# ADC_Board_Left.net
KiCad netlist of a schematic drawn in EAGLE
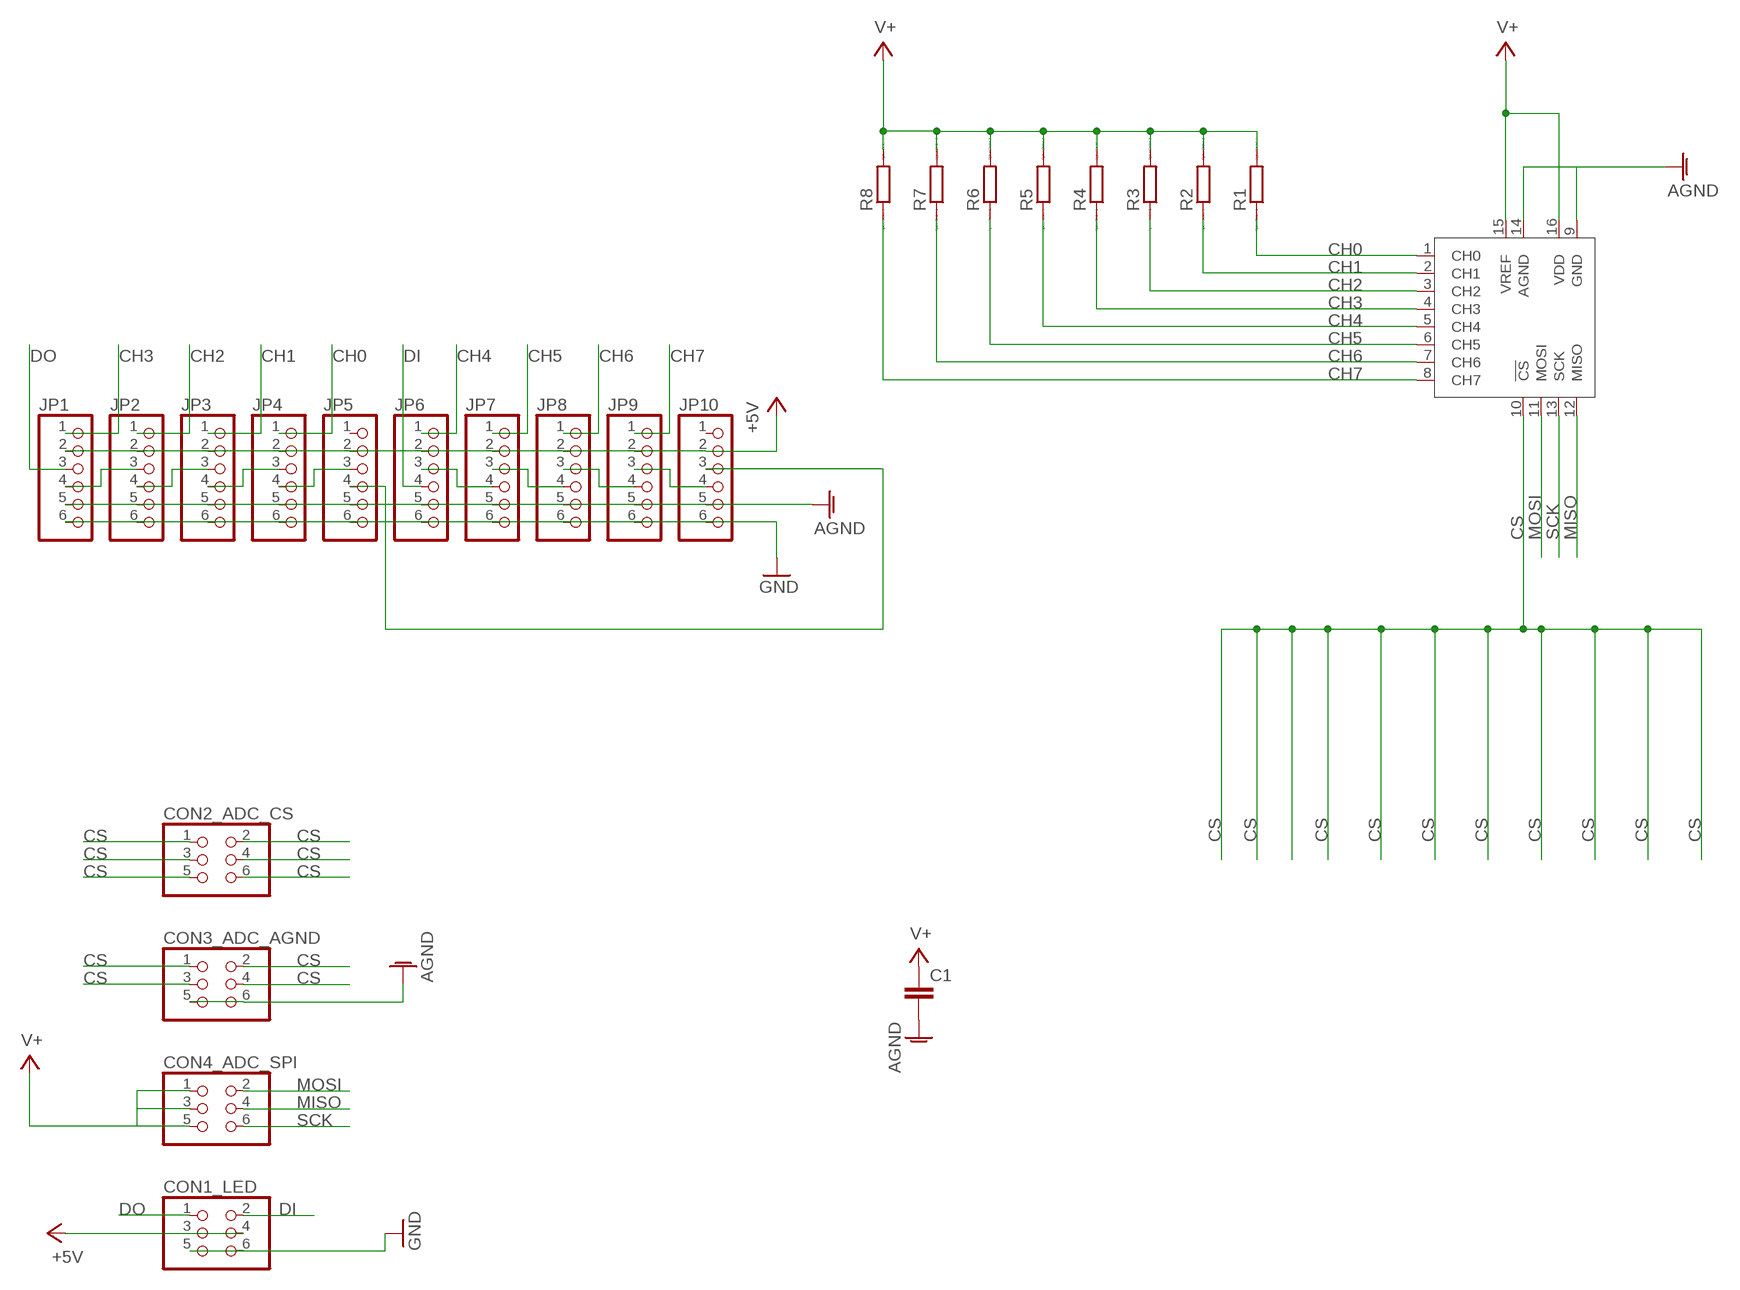
[diagram p0: schematic, sheet 1]

(export (version "E")
  (design (tool "Eeschema 10.0.6"))
  (components
    (comp (ref "C1")
      (value "C-EU050-025X075")
      (footprint "eagle-import:C050-025X075")
      (libsource (lib "eagle-import") (part "C-EU050-025X075"))
    )
    (comp (ref "CON1_LED")
      (value "PINHD-2X3")
      (footprint "eagle-import:2X03")
      (libsource (lib "eagle-import") (part "PINHD-2X3"))
    )
    (comp (ref "CON2_ADC_CS")
      (value "PINHD-2X3")
      (footprint "eagle-import:2X03")
      (libsource (lib "eagle-import") (part "PINHD-2X3"))
    )
    (comp (ref "CON3_ADC_AGND")
      (value "PINHD-2X3")
      (footprint "eagle-import:2X03")
      (libsource (lib "eagle-import") (part "PINHD-2X3"))
    )
    (comp (ref "CON4_ADC_SPI")
      (value "PINHD-2X3")
      (footprint "eagle-import:2X03")
      (libsource (lib "eagle-import") (part "PINHD-2X3"))
    )
    (comp (ref "JP1")
      (value "PINHD-1X6")
      (footprint "eagle-import:1X06")
      (libsource (lib "eagle-import") (part "PINHD-1X6"))
    )
    (comp (ref "JP2")
      (value "PINHD-1X6")
      (footprint "eagle-import:1X06")
      (libsource (lib "eagle-import") (part "PINHD-1X6"))
    )
    (comp (ref "JP3")
      (value "PINHD-1X6")
      (footprint "eagle-import:1X06")
      (libsource (lib "eagle-import") (part "PINHD-1X6"))
    )
    (comp (ref "JP4")
      (value "PINHD-1X6")
      (footprint "eagle-import:1X06")
      (libsource (lib "eagle-import") (part "PINHD-1X6"))
    )
    (comp (ref "JP5")
      (value "PINHD-1X6")
      (footprint "eagle-import:1X06")
      (libsource (lib "eagle-import") (part "PINHD-1X6"))
    )
    (comp (ref "JP6")
      (value "PINHD-1X6")
      (footprint "eagle-import:1X06")
      (libsource (lib "eagle-import") (part "PINHD-1X6"))
    )
    (comp (ref "JP7")
      (value "PINHD-1X6")
      (footprint "eagle-import:1X06")
      (libsource (lib "eagle-import") (part "PINHD-1X6"))
    )
    (comp (ref "JP8")
      (value "PINHD-1X6")
      (footprint "eagle-import:1X06")
      (libsource (lib "eagle-import") (part "PINHD-1X6"))
    )
    (comp (ref "JP9")
      (value "PINHD-1X6")
      (footprint "eagle-import:1X06")
      (libsource (lib "eagle-import") (part "PINHD-1X6"))
    )
    (comp (ref "JP10")
      (value "PINHD-1X6")
      (footprint "eagle-import:1X06")
      (libsource (lib "eagle-import") (part "PINHD-1X6"))
    )
    (comp (ref "R1")
      (value "R-EU_0617_22")
      (footprint "eagle-import:0617_22")
      (libsource (lib "eagle-import") (part "R-EU_0617_22"))
    )
    (comp (ref "R2")
      (value "R-EU_0617_22")
      (footprint "eagle-import:0617_22")
      (libsource (lib "eagle-import") (part "R-EU_0617_22"))
    )
    (comp (ref "R3")
      (value "R-EU_0617_22")
      (footprint "eagle-import:0617_22")
      (libsource (lib "eagle-import") (part "R-EU_0617_22"))
    )
    (comp (ref "R4")
      (value "R-EU_0617_22")
      (footprint "eagle-import:0617_22")
      (libsource (lib "eagle-import") (part "R-EU_0617_22"))
    )
    (comp (ref "R5")
      (value "R-EU_0617_22")
      (footprint "eagle-import:0617_22")
      (libsource (lib "eagle-import") (part "R-EU_0617_22"))
    )
    (comp (ref "R6")
      (value "R-EU_0617_22")
      (footprint "eagle-import:0617_22")
      (libsource (lib "eagle-import") (part "R-EU_0617_22"))
    )
    (comp (ref "R7")
      (value "R-EU_0617_22")
      (footprint "eagle-import:0617_22")
      (libsource (lib "eagle-import") (part "R-EU_0617_22"))
    )
    (comp (ref "R8")
      (value "R-EU_0617_22")
      (footprint "eagle-import:0617_22")
      (libsource (lib "eagle-import") (part "R-EU_0617_22"))
    )
    (comp (ref "U$1")
      (value "MCP3008P")
      (footprint "eagle-import:DIL16")
      (libsource (lib "eagle-import") (part "MCP3008P"))
    )
  )
  (nets
    (net (code "1") (name "+5V") (class "Default")
      (node (ref "CON1_LED") (pin "3") (pinfunction "3_3") (pintype "passive"))
      (node (ref "CON1_LED") (pin "4") (pinfunction "4_4") (pintype "passive"))
      (node (ref "JP1") (pin "2") (pinfunction "2_2") (pintype "passive"))
      (node (ref "JP10") (pin "2") (pinfunction "2_2") (pintype "passive"))
      (node (ref "JP2") (pin "2") (pinfunction "2_2") (pintype "passive"))
      (node (ref "JP3") (pin "2") (pinfunction "2_2") (pintype "passive"))
      (node (ref "JP4") (pin "2") (pinfunction "2_2") (pintype "passive"))
      (node (ref "JP5") (pin "2") (pinfunction "2_2") (pintype "passive"))
      (node (ref "JP6") (pin "2") (pinfunction "2_2") (pintype "passive"))
      (node (ref "JP7") (pin "2") (pinfunction "2_2") (pintype "passive"))
      (node (ref "JP8") (pin "2") (pinfunction "2_2") (pintype "passive"))
      (node (ref "JP9") (pin "2") (pinfunction "2_2") (pintype "passive"))
    )
    (net (code "2") (name "/CH0") (class "Default")
      (node (ref "JP4") (pin "1") (pinfunction "1_1") (pintype "passive"))
      (node (ref "R1") (pin "1") (pinfunction "1_1") (pintype "passive"))
      (node (ref "U$1") (pin "1") (pinfunction "CH0_1") (pintype "input"))
    )
    (net (code "3") (name "/CH1") (class "Default")
      (node (ref "JP3") (pin "1") (pinfunction "1_1") (pintype "passive"))
      (node (ref "R2") (pin "1") (pinfunction "1_1") (pintype "passive"))
      (node (ref "U$1") (pin "2") (pinfunction "CH1_2") (pintype "input"))
    )
    (net (code "4") (name "/CH2") (class "Default")
      (node (ref "JP2") (pin "1") (pinfunction "1_1") (pintype "passive"))
      (node (ref "R3") (pin "1") (pinfunction "1_1") (pintype "passive"))
      (node (ref "U$1") (pin "3") (pinfunction "CH2_3") (pintype "input"))
    )
    (net (code "5") (name "/CH3") (class "Default")
      (node (ref "JP1") (pin "1") (pinfunction "1_1") (pintype "passive"))
      (node (ref "R4") (pin "1") (pinfunction "1_1") (pintype "passive"))
      (node (ref "U$1") (pin "4") (pinfunction "CH3_4") (pintype "input"))
    )
    (net (code "6") (name "/CH4") (class "Default")
      (node (ref "JP6") (pin "1") (pinfunction "1_1") (pintype "passive"))
      (node (ref "R5") (pin "1") (pinfunction "1_1") (pintype "passive"))
      (node (ref "U$1") (pin "5") (pinfunction "CH4_5") (pintype "input"))
    )
    (net (code "7") (name "/CH5") (class "Default")
      (node (ref "JP7") (pin "1") (pinfunction "1_1") (pintype "passive"))
      (node (ref "R6") (pin "1") (pinfunction "1_1") (pintype "passive"))
      (node (ref "U$1") (pin "6") (pinfunction "CH5_6") (pintype "input"))
    )
    (net (code "8") (name "/CH6") (class "Default")
      (node (ref "JP8") (pin "1") (pinfunction "1_1") (pintype "passive"))
      (node (ref "R7") (pin "1") (pinfunction "1_1") (pintype "passive"))
      (node (ref "U$1") (pin "7") (pinfunction "CH6_7") (pintype "input"))
    )
    (net (code "9") (name "/CH7") (class "Default")
      (node (ref "JP9") (pin "1") (pinfunction "1_1") (pintype "passive"))
      (node (ref "R8") (pin "1") (pinfunction "1_1") (pintype "passive"))
      (node (ref "U$1") (pin "8") (pinfunction "CH7_8") (pintype "input"))
    )
    (net (code "10") (name "/CS") (class "Default")
      (node (ref "CON2_ADC_CS") (pin "1") (pinfunction "1_1") (pintype "passive"))
      (node (ref "CON2_ADC_CS") (pin "2") (pinfunction "2_2") (pintype "passive"))
      (node (ref "CON2_ADC_CS") (pin "3") (pinfunction "3_3") (pintype "passive"))
      (node (ref "CON2_ADC_CS") (pin "4") (pinfunction "4_4") (pintype "passive"))
      (node (ref "CON2_ADC_CS") (pin "5") (pinfunction "5_5") (pintype "passive"))
      (node (ref "CON2_ADC_CS") (pin "6") (pinfunction "6_6") (pintype "passive"))
      (node (ref "CON3_ADC_AGND") (pin "1") (pinfunction "1_1") (pintype "passive"))
      (node (ref "CON3_ADC_AGND") (pin "2") (pinfunction "2_2") (pintype "passive"))
      (node (ref "CON3_ADC_AGND") (pin "3") (pinfunction "3_3") (pintype "passive"))
      (node (ref "CON3_ADC_AGND") (pin "4") (pinfunction "4_4") (pintype "passive"))
      (node (ref "U$1") (pin "10") (pinfunction "~{CS}_10") (pintype "input"))
    )
    (net (code "11") (name "/DI") (class "Default")
      (node (ref "CON1_LED") (pin "2") (pinfunction "2_2") (pintype "passive"))
      (node (ref "JP6") (pin "4") (pinfunction "4_4") (pintype "passive"))
    )
    (net (code "12") (name "/DO") (class "Default")
      (node (ref "CON1_LED") (pin "1") (pinfunction "1_1") (pintype "passive"))
      (node (ref "JP1") (pin "3") (pinfunction "3_3") (pintype "passive"))
    )
    (net (code "13") (name "/MISO") (class "Default")
      (node (ref "CON4_ADC_SPI") (pin "4") (pinfunction "4_4") (pintype "passive"))
      (node (ref "U$1") (pin "12") (pinfunction "MISO_12") (pintype "output"))
    )
    (net (code "14") (name "/MOSI") (class "Default")
      (node (ref "CON4_ADC_SPI") (pin "2") (pinfunction "2_2") (pintype "passive"))
      (node (ref "U$1") (pin "11") (pinfunction "MOSI_11") (pintype "input"))
    )
    (net (code "15") (name "/SCK") (class "Default")
      (node (ref "CON4_ADC_SPI") (pin "6") (pinfunction "6_6") (pintype "passive"))
      (node (ref "U$1") (pin "13") (pinfunction "SCK_13") (pintype "input"))
    )
    (net (code "16") (name "AGND") (class "Default")
      (node (ref "C1") (pin "2") (pinfunction "2_2") (pintype "passive"))
      (node (ref "CON3_ADC_AGND") (pin "5") (pinfunction "5_5") (pintype "passive"))
      (node (ref "CON3_ADC_AGND") (pin "6") (pinfunction "6_6") (pintype "passive"))
      (node (ref "JP1") (pin "5") (pinfunction "5_5") (pintype "passive"))
      (node (ref "JP10") (pin "5") (pinfunction "5_5") (pintype "passive"))
      (node (ref "JP2") (pin "5") (pinfunction "5_5") (pintype "passive"))
      (node (ref "JP3") (pin "5") (pinfunction "5_5") (pintype "passive"))
      (node (ref "JP4") (pin "5") (pinfunction "5_5") (pintype "passive"))
      (node (ref "JP5") (pin "5") (pinfunction "5_5") (pintype "passive"))
      (node (ref "JP6") (pin "5") (pinfunction "5_5") (pintype "passive"))
      (node (ref "JP7") (pin "5") (pinfunction "5_5") (pintype "passive"))
      (node (ref "JP8") (pin "5") (pinfunction "5_5") (pintype "passive"))
      (node (ref "JP9") (pin "5") (pinfunction "5_5") (pintype "passive"))
      (node (ref "U$1") (pin "14") (pinfunction "AGND_14") (pintype "power_in"))
      (node (ref "U$1") (pin "9") (pinfunction "GND_9") (pintype "power_in"))
    )
    (net (code "17") (name "GND") (class "Default")
      (node (ref "CON1_LED") (pin "5") (pinfunction "5_5") (pintype "passive"))
      (node (ref "CON1_LED") (pin "6") (pinfunction "6_6") (pintype "passive"))
      (node (ref "JP1") (pin "6") (pinfunction "6_6") (pintype "passive"))
      (node (ref "JP10") (pin "6") (pinfunction "6_6") (pintype "passive"))
      (node (ref "JP2") (pin "6") (pinfunction "6_6") (pintype "passive"))
      (node (ref "JP3") (pin "6") (pinfunction "6_6") (pintype "passive"))
      (node (ref "JP4") (pin "6") (pinfunction "6_6") (pintype "passive"))
      (node (ref "JP5") (pin "6") (pinfunction "6_6") (pintype "passive"))
      (node (ref "JP6") (pin "6") (pinfunction "6_6") (pintype "passive"))
      (node (ref "JP7") (pin "6") (pinfunction "6_6") (pintype "passive"))
      (node (ref "JP8") (pin "6") (pinfunction "6_6") (pintype "passive"))
      (node (ref "JP9") (pin "6") (pinfunction "6_6") (pintype "passive"))
    )
    (net (code "18") (name "Net-(JP1-Pad4)") (class "Default")
      (node (ref "JP1") (pin "4") (pinfunction "4_4") (pintype "passive"))
      (node (ref "JP2") (pin "3") (pinfunction "3_3") (pintype "passive"))
    )
    (net (code "19") (name "Net-(JP2-Pad4)") (class "Default")
      (node (ref "JP2") (pin "4") (pinfunction "4_4") (pintype "passive"))
      (node (ref "JP3") (pin "3") (pinfunction "3_3") (pintype "passive"))
    )
    (net (code "20") (name "Net-(JP3-Pad4)") (class "Default")
      (node (ref "JP3") (pin "4") (pinfunction "4_4") (pintype "passive"))
      (node (ref "JP4") (pin "3") (pinfunction "3_3") (pintype "passive"))
    )
    (net (code "21") (name "Net-(JP4-Pad4)") (class "Default")
      (node (ref "JP4") (pin "4") (pinfunction "4_4") (pintype "passive"))
      (node (ref "JP5") (pin "3") (pinfunction "3_3") (pintype "passive"))
    )
    (net (code "22") (name "Net-(JP6-Pad3)") (class "Default")
      (node (ref "JP6") (pin "3") (pinfunction "3_3") (pintype "passive"))
      (node (ref "JP7") (pin "4") (pinfunction "4_4") (pintype "passive"))
    )
    (net (code "23") (name "Net-(JP7-Pad3)") (class "Default")
      (node (ref "JP7") (pin "3") (pinfunction "3_3") (pintype "passive"))
      (node (ref "JP8") (pin "4") (pinfunction "4_4") (pintype "passive"))
    )
    (net (code "24") (name "Net-(JP8-Pad3)") (class "Default")
      (node (ref "JP8") (pin "3") (pinfunction "3_3") (pintype "passive"))
      (node (ref "JP9") (pin "4") (pinfunction "4_4") (pintype "passive"))
    )
    (net (code "25") (name "Net-(JP10-Pad3)") (class "Default")
      (node (ref "JP10") (pin "3") (pinfunction "3_3") (pintype "passive"))
      (node (ref "JP5") (pin "4") (pinfunction "4_4") (pintype "passive"))
    )
    (net (code "26") (name "Net-(JP10-Pad4)") (class "Default")
      (node (ref "JP10") (pin "4") (pinfunction "4_4") (pintype "passive"))
      (node (ref "JP9") (pin "3") (pinfunction "3_3") (pintype "passive"))
    )
    (net (code "27") (name "V+") (class "Default")
      (node (ref "C1") (pin "1") (pinfunction "1_1") (pintype "passive"))
      (node (ref "CON4_ADC_SPI") (pin "1") (pinfunction "1_1") (pintype "passive"))
      (node (ref "CON4_ADC_SPI") (pin "3") (pinfunction "3_3") (pintype "passive"))
      (node (ref "CON4_ADC_SPI") (pin "5") (pinfunction "5_5") (pintype "passive"))
      (node (ref "R1") (pin "2") (pinfunction "2_2") (pintype "passive"))
      (node (ref "R2") (pin "2") (pinfunction "2_2") (pintype "passive"))
      (node (ref "R3") (pin "2") (pinfunction "2_2") (pintype "passive"))
      (node (ref "R4") (pin "2") (pinfunction "2_2") (pintype "passive"))
      (node (ref "R5") (pin "2") (pinfunction "2_2") (pintype "passive"))
      (node (ref "R6") (pin "2") (pinfunction "2_2") (pintype "passive"))
      (node (ref "R7") (pin "2") (pinfunction "2_2") (pintype "passive"))
      (node (ref "R8") (pin "2") (pinfunction "2_2") (pintype "passive"))
      (node (ref "U$1") (pin "15") (pinfunction "VREF_15") (pintype "power_in"))
      (node (ref "U$1") (pin "16") (pinfunction "VDD_16") (pintype "power_in"))
    )
    (net (code "28") (name "unconnected-(JP5-Pad1)") (class "Default")
      (node (ref "JP5") (pin "1") (pinfunction "1_1") (pintype "passive"))
    )
    (net (code "29") (name "unconnected-(JP10-Pad1)") (class "Default")
      (node (ref "JP10") (pin "1") (pinfunction "1_1") (pintype "passive"))
    )
  )
)
